# vn808cm_bo.net
KiCad netlist of a schematic drawn in EAGLE
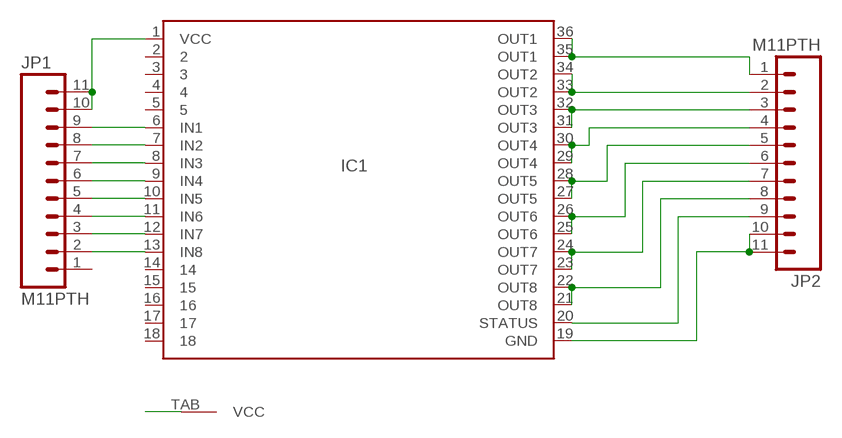
[diagram p0: schematic, sheet 1]

(export (version "E")
  (design (tool "Eeschema 10.0.6"))
  (components
    (comp (ref "IC1")
      (value "VN808CM-E")
      (footprint "eagle-import:POWERSO-36")
      (libsource (lib "eagle-import") (part "VN808CM-E"))
    )
    (comp (ref "JP1")
      (value "M11PTH")
      (footprint "eagle-import:1X11")
      (libsource (lib "eagle-import") (part "M11PTH"))
    )
    (comp (ref "JP2")
      (value "M11PTH")
      (footprint "eagle-import:1X11")
      (libsource (lib "eagle-import") (part "M11PTH"))
    )
  )
  (nets
    (net (code "1") (name "/VCC") (class "Default")
      (node (ref "IC1") (pin "1") (pinfunction "VCC_1") (pintype "power_in"))
      (node (ref "IC1") (pin "TAB") (pinfunction "VCC_TAB") (pintype "power_in"))
      (node (ref "JP1") (pin "10") (pinfunction "10_10") (pintype "passive"))
      (node (ref "JP1") (pin "11") (pinfunction "11_11") (pintype "passive"))
    )
    (net (code "2") (name "Net-(IC1-GND)") (class "Default")
      (node (ref "IC1") (pin "19") (pinfunction "GND_19") (pintype "power_in"))
      (node (ref "JP2") (pin "10") (pinfunction "10_10") (pintype "passive"))
      (node (ref "JP2") (pin "11") (pinfunction "11_11") (pintype "passive"))
    )
    (net (code "3") (name "Net-(IC1-IN1)") (class "Default")
      (node (ref "IC1") (pin "6") (pinfunction "IN1_6") (pintype "input"))
      (node (ref "JP1") (pin "9") (pinfunction "9_9") (pintype "passive"))
    )
    (net (code "4") (name "Net-(IC1-IN2)") (class "Default")
      (node (ref "IC1") (pin "7") (pinfunction "IN2_7") (pintype "input"))
      (node (ref "JP1") (pin "8") (pinfunction "8_8") (pintype "passive"))
    )
    (net (code "5") (name "Net-(IC1-IN3)") (class "Default")
      (node (ref "IC1") (pin "8") (pinfunction "IN3_8") (pintype "input"))
      (node (ref "JP1") (pin "7") (pinfunction "7_7") (pintype "passive"))
    )
    (net (code "6") (name "Net-(IC1-IN4)") (class "Default")
      (node (ref "IC1") (pin "9") (pinfunction "IN4_9") (pintype "input"))
      (node (ref "JP1") (pin "6") (pinfunction "6_6") (pintype "passive"))
    )
    (net (code "7") (name "Net-(IC1-IN5)") (class "Default")
      (node (ref "IC1") (pin "10") (pinfunction "IN5_10") (pintype "input"))
      (node (ref "JP1") (pin "5") (pinfunction "5_5") (pintype "passive"))
    )
    (net (code "8") (name "Net-(IC1-IN6)") (class "Default")
      (node (ref "IC1") (pin "11") (pinfunction "IN6_11") (pintype "input"))
      (node (ref "JP1") (pin "4") (pinfunction "4_4") (pintype "passive"))
    )
    (net (code "9") (name "Net-(IC1-IN7)") (class "Default")
      (node (ref "IC1") (pin "12") (pinfunction "IN7_12") (pintype "input"))
      (node (ref "JP1") (pin "3") (pinfunction "3_3") (pintype "passive"))
    )
    (net (code "10") (name "Net-(IC1-IN8)") (class "Default")
      (node (ref "IC1") (pin "13") (pinfunction "IN8_13") (pintype "input"))
      (node (ref "JP1") (pin "2") (pinfunction "2_2") (pintype "passive"))
    )
    (net (code "11") (name "Net-(IC1-OUT1-Pad35)") (class "Default")
      (node (ref "IC1") (pin "35") (pinfunction "OUT1_35") (pintype "output"))
      (node (ref "IC1") (pin "36") (pinfunction "OUT1_36") (pintype "output"))
      (node (ref "JP2") (pin "1") (pinfunction "1_1") (pintype "passive"))
    )
    (net (code "12") (name "Net-(IC1-OUT2-Pad33)") (class "Default")
      (node (ref "IC1") (pin "33") (pinfunction "OUT2_33") (pintype "output"))
      (node (ref "IC1") (pin "34") (pinfunction "OUT2_34") (pintype "output"))
      (node (ref "JP2") (pin "2") (pinfunction "2_2") (pintype "passive"))
    )
    (net (code "13") (name "Net-(IC1-OUT3-Pad31)") (class "Default")
      (node (ref "IC1") (pin "31") (pinfunction "OUT3_31") (pintype "output"))
      (node (ref "IC1") (pin "32") (pinfunction "OUT3_32") (pintype "output"))
      (node (ref "JP2") (pin "3") (pinfunction "3_3") (pintype "passive"))
    )
    (net (code "14") (name "Net-(IC1-OUT4-Pad29)") (class "Default")
      (node (ref "IC1") (pin "29") (pinfunction "OUT4_29") (pintype "output"))
      (node (ref "IC1") (pin "30") (pinfunction "OUT4_30") (pintype "output"))
      (node (ref "JP2") (pin "4") (pinfunction "4_4") (pintype "passive"))
    )
    (net (code "15") (name "Net-(IC1-OUT5-Pad27)") (class "Default")
      (node (ref "IC1") (pin "27") (pinfunction "OUT5_27") (pintype "output"))
      (node (ref "IC1") (pin "28") (pinfunction "OUT5_28") (pintype "output"))
      (node (ref "JP2") (pin "5") (pinfunction "5_5") (pintype "passive"))
    )
    (net (code "16") (name "Net-(IC1-OUT6-Pad25)") (class "Default")
      (node (ref "IC1") (pin "25") (pinfunction "OUT6_25") (pintype "output"))
      (node (ref "IC1") (pin "26") (pinfunction "OUT6_26") (pintype "output"))
      (node (ref "JP2") (pin "6") (pinfunction "6_6") (pintype "passive"))
    )
    (net (code "17") (name "Net-(IC1-OUT7-Pad23)") (class "Default")
      (node (ref "IC1") (pin "23") (pinfunction "OUT7_23") (pintype "output"))
      (node (ref "IC1") (pin "24") (pinfunction "OUT7_24") (pintype "output"))
      (node (ref "JP2") (pin "7") (pinfunction "7_7") (pintype "passive"))
    )
    (net (code "18") (name "Net-(IC1-OUT8-Pad21)") (class "Default")
      (node (ref "IC1") (pin "21") (pinfunction "OUT8_21") (pintype "output"))
      (node (ref "IC1") (pin "22") (pinfunction "OUT8_22") (pintype "output"))
      (node (ref "JP2") (pin "8") (pinfunction "8_8") (pintype "passive"))
    )
    (net (code "19") (name "Net-(IC1-STATUS)") (class "Default")
      (node (ref "IC1") (pin "20") (pinfunction "STATUS_20") (pintype "output"))
      (node (ref "JP2") (pin "9") (pinfunction "9_9") (pintype "passive"))
    )
    (net (code "20") (name "unconnected-(IC1-Pad2)") (class "Default")
      (node (ref "IC1") (pin "2") (pinfunction "2_2") (pintype "no_connect"))
    )
    (net (code "21") (name "unconnected-(IC1-Pad3)") (class "Default")
      (node (ref "IC1") (pin "3") (pinfunction "3_3") (pintype "no_connect"))
    )
    (net (code "22") (name "unconnected-(IC1-Pad4)") (class "Default")
      (node (ref "IC1") (pin "4") (pinfunction "4_4") (pintype "no_connect"))
    )
    (net (code "23") (name "unconnected-(IC1-Pad5)") (class "Default")
      (node (ref "IC1") (pin "5") (pinfunction "5_5") (pintype "no_connect"))
    )
    (net (code "24") (name "unconnected-(IC1-Pad14)") (class "Default")
      (node (ref "IC1") (pin "14") (pinfunction "14_14") (pintype "no_connect"))
    )
    (net (code "25") (name "unconnected-(IC1-Pad15)") (class "Default")
      (node (ref "IC1") (pin "15") (pinfunction "15_15") (pintype "no_connect"))
    )
    (net (code "26") (name "unconnected-(IC1-Pad16)") (class "Default")
      (node (ref "IC1") (pin "16") (pinfunction "16_16") (pintype "no_connect"))
    )
    (net (code "27") (name "unconnected-(IC1-Pad17)") (class "Default")
      (node (ref "IC1") (pin "17") (pinfunction "17_17") (pintype "no_connect"))
    )
    (net (code "28") (name "unconnected-(IC1-Pad18)") (class "Default")
      (node (ref "IC1") (pin "18") (pinfunction "18_18") (pintype "no_connect"))
    )
    (net (code "29") (name "unconnected-(JP1-Pad1)") (class "Default")
      (node (ref "JP1") (pin "1") (pinfunction "1_1") (pintype "passive"))
    )
  )
)
